# lab2_Kondrashova_buck_boost.net
KiCad netlist of a schematic drawn in Altium Designer
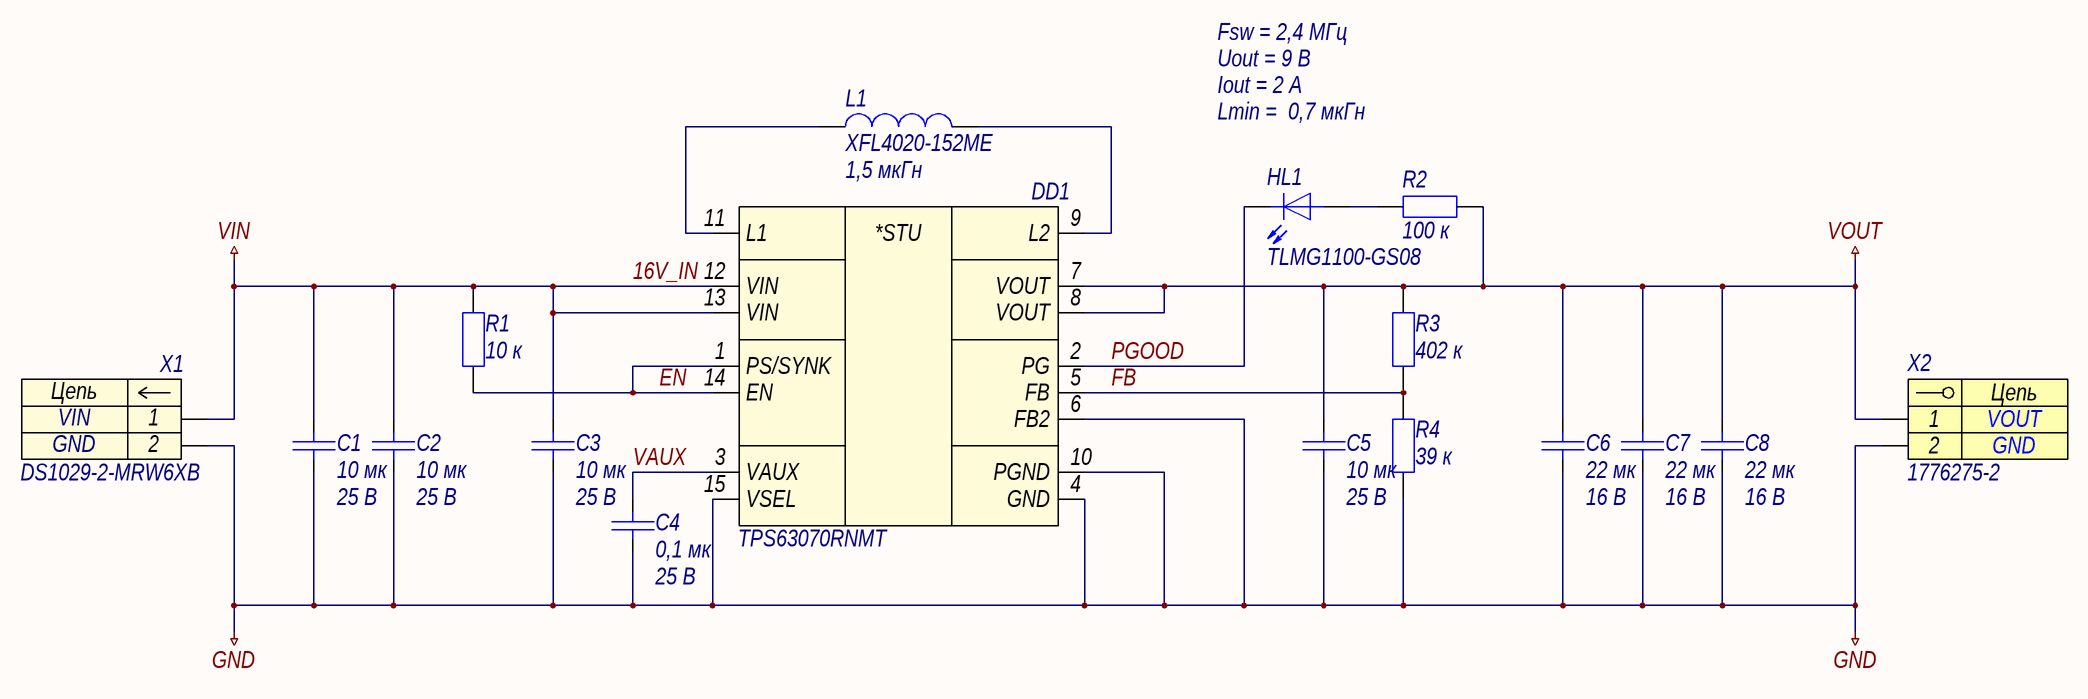
[diagram p0: lab2_Kondrashova_buck_boost.SchDoc]

(export (version "E")
  (design (tool "Eeschema 10.0.6"))
  (components
    (comp (ref "C1")
      (value "10 мк")
      (footprint "C1206")
      (description "=Описание")
      (fields (field (name "НАПРЯЖЕНИЕ") "25 В"))
      (libsource (lib "Database_Students") (part "C-NONPOLAR"))
    )
    (comp (ref "C2")
      (value "10 мк")
      (footprint "C1206")
      (description "=Описание")
      (fields (field (name "НАПРЯЖЕНИЕ") "25 В"))
      (libsource (lib "Database_Students") (part "C-NONPOLAR"))
    )
    (comp (ref "C3")
      (value "10 мк")
      (footprint "C0603")
      (description "=Описание")
      (fields (field (name "НАПРЯЖЕНИЕ") "25 В"))
      (libsource (lib "Database_Students") (part "C-NONPOLAR"))
    )
    (comp (ref "C4")
      (value "0,1 мк")
      (footprint "C0402")
      (description "=Описание")
      (fields (field (name "НАПРЯЖЕНИЕ") "25 В"))
      (libsource (lib "Database_Students") (part "C-NONPOLAR"))
    )
    (comp (ref "C5")
      (value "10 мк")
      (footprint "C0603")
      (description "=Описание")
      (fields (field (name "НАПРЯЖЕНИЕ") "25 В"))
      (libsource (lib "Database_Students") (part "C-NONPOLAR"))
    )
    (comp (ref "C6")
      (value "22 мк")
      (footprint "C0805")
      (description "=Описание")
      (fields (field (name "НАПРЯЖЕНИЕ") "16 В"))
      (libsource (lib "Database_Students") (part "C-NONPOLAR"))
    )
    (comp (ref "C7")
      (value "22 мк")
      (footprint "C0805")
      (description "=Описание")
      (fields (field (name "НАПРЯЖЕНИЕ") "16 В"))
      (libsource (lib "Database_Students") (part "C-NONPOLAR"))
    )
    (comp (ref "C8")
      (value "22 мк")
      (footprint "C0805")
      (description "=Описание")
      (fields (field (name "НАПРЯЖЕНИЕ") "16 В"))
      (libsource (lib "Database_Students") (part "C-NONPOLAR"))
    )
    (comp (ref "DD1")
      (value "TPS63070RNMT")
      (footprint "VQFN-HR-15")
      (description "=Описание")
      (libsource (lib "Database_Students") (part "TPS63070RNMT"))
    )
    (comp (ref "HL1")
      (value "TLMG1100-GS08")
      (footprint "HL0603")
      (description "=Описание")
      (libsource (lib "Database_Students") (part "HL-COMMON"))
    )
    (comp (ref "L1")
      (value "XFL4020-152ME")
      (footprint "XFL-2-400X400X210")
      (description "=Описание")
      (fields (field (name "ИНДУКТИВНОСТЬ") "1,5 мкГн"))
      (libsource (lib "Database_Students") (part "INDUCTOR-COMMON"))
    )
    (comp (ref "R1")
      (value "10 к")
      (footprint "R0603")
      (description "=Описание")
      (libsource (lib "Database_Students") (part "R-COMMON"))
    )
    (comp (ref "R2")
      (value "100 к")
      (footprint "R0603")
      (description "=Описание")
      (libsource (lib "Database_Students") (part "R-COMMON"))
    )
    (comp (ref "R3")
      (value "402 к")
      (footprint "R0603")
      (description "=Описание")
      (libsource (lib "Database_Students") (part "R-COMMON"))
    )
    (comp (ref "R4")
      (value "39 к")
      (footprint "R0603")
      (description "=Описание")
      (libsource (lib "Database_Students") (part "R-COMMON"))
    )
    (comp (ref "X1")
      (value "DS1029-2-MRW6XB")
      (footprint "DS1029-2-MRW6XB")
      (description "=Описание")
      (libsource (lib "Database_Students") (part "HEADER-2-PLG"))
    )
    (comp (ref "X2")
      (value "1776275-2")
      (footprint "1776275-2")
      (description "=Описание")
      (libsource (lib "Database_Students") (part "HEADER-2-TRM"))
    )
  )
  (nets
    (net (code "1") (name "/EN") (class "Default")
      (node (ref "DD1") (pin "1") (pinfunction "PS/SYNK_1") (pintype "passive"))
      (node (ref "DD1") (pin "14") (pinfunction "EN_14") (pintype "passive"))
      (node (ref "R1") (pin "2") (pinfunction "2_2") (pintype "passive"))
    )
    (net (code "2") (name "/FB") (class "Default")
      (node (ref "DD1") (pin "5") (pinfunction "FB_5") (pintype "passive"))
      (node (ref "R3") (pin "2") (pinfunction "2_2") (pintype "passive"))
      (node (ref "R4") (pin "1") (pinfunction "1_1") (pintype "passive"))
    )
    (net (code "3") (name "/PGOOD") (class "Default")
      (node (ref "DD1") (pin "2") (pinfunction "PG_2") (pintype "passive"))
      (node (ref "HL1") (pin "1") (pinfunction "1_1") (pintype "passive"))
    )
    (net (code "4") (name "/VAUX") (class "Default")
      (node (ref "C4") (pin "1") (pinfunction "1_1") (pintype "passive"))
      (node (ref "DD1") (pin "3") (pinfunction "VAUX_3") (pintype "passive"))
    )
    (net (code "5") (name "GND") (class "Default")
      (node (ref "C1") (pin "2") (pinfunction "2_2") (pintype "passive"))
      (node (ref "C2") (pin "2") (pinfunction "2_2") (pintype "passive"))
      (node (ref "C3") (pin "2") (pinfunction "2_2") (pintype "passive"))
      (node (ref "C4") (pin "2") (pinfunction "2_2") (pintype "passive"))
      (node (ref "C5") (pin "2") (pinfunction "2_2") (pintype "passive"))
      (node (ref "C6") (pin "1") (pinfunction "1_1") (pintype "passive"))
      (node (ref "C7") (pin "1") (pinfunction "1_1") (pintype "passive"))
      (node (ref "C8") (pin "1") (pinfunction "1_1") (pintype "passive"))
      (node (ref "DD1") (pin "10") (pinfunction "PGND_10") (pintype "passive"))
      (node (ref "DD1") (pin "15") (pinfunction "VSEL_15") (pintype "passive"))
      (node (ref "DD1") (pin "4") (pinfunction "GND_4") (pintype "passive"))
      (node (ref "DD1") (pin "6") (pinfunction "FB2_6") (pintype "passive"))
      (node (ref "R4") (pin "2") (pinfunction "2_2") (pintype "passive"))
      (node (ref "X1") (pin "2") (pinfunction "2_2") (pintype "passive"))
      (node (ref "X2") (pin "2") (pinfunction "2_2") (pintype "passive"))
    )
    (net (code "6") (name "Net-(DD1-L1)") (class "Default")
      (node (ref "DD1") (pin "11") (pinfunction "L1_11") (pintype "passive"))
      (node (ref "L1") (pin "1") (pinfunction "1_1") (pintype "passive"))
    )
    (net (code "7") (name "Net-(DD1-L2)") (class "Default")
      (node (ref "DD1") (pin "9") (pinfunction "L2_9") (pintype "passive"))
      (node (ref "L1") (pin "2") (pinfunction "2_2") (pintype "passive"))
    )
    (net (code "8") (name "Net-(HL1-Pad2)") (class "Default")
      (node (ref "HL1") (pin "2") (pinfunction "2_2") (pintype "passive"))
      (node (ref "R2") (pin "2") (pinfunction "2_2") (pintype "passive"))
    )
    (net (code "9") (name "VIN") (class "Default")
      (node (ref "C1") (pin "1") (pinfunction "1_1") (pintype "passive"))
      (node (ref "C2") (pin "1") (pinfunction "1_1") (pintype "passive"))
      (node (ref "C3") (pin "1") (pinfunction "1_1") (pintype "passive"))
      (node (ref "DD1") (pin "12") (pinfunction "VIN_12") (pintype "passive"))
      (node (ref "DD1") (pin "13") (pinfunction "VIN_13") (pintype "passive"))
      (node (ref "R1") (pin "1") (pinfunction "1_1") (pintype "passive"))
      (node (ref "X1") (pin "1") (pinfunction "1_1") (pintype "passive"))
    )
    (net (code "10") (name "VOUT") (class "Default")
      (node (ref "C5") (pin "1") (pinfunction "1_1") (pintype "passive"))
      (node (ref "C6") (pin "2") (pinfunction "2_2") (pintype "passive"))
      (node (ref "C7") (pin "2") (pinfunction "2_2") (pintype "passive"))
      (node (ref "C8") (pin "2") (pinfunction "2_2") (pintype "passive"))
      (node (ref "DD1") (pin "7") (pinfunction "VOUT_7") (pintype "passive"))
      (node (ref "DD1") (pin "8") (pinfunction "VOUT_8") (pintype "passive"))
      (node (ref "R2") (pin "1") (pinfunction "1_1") (pintype "passive"))
      (node (ref "R3") (pin "1") (pinfunction "1_1") (pintype "passive"))
      (node (ref "X2") (pin "1") (pinfunction "1_1") (pintype "passive"))
    )
  )
)
